# ft4222h.net
KiCad netlist of a schematic drawn in EAGLE
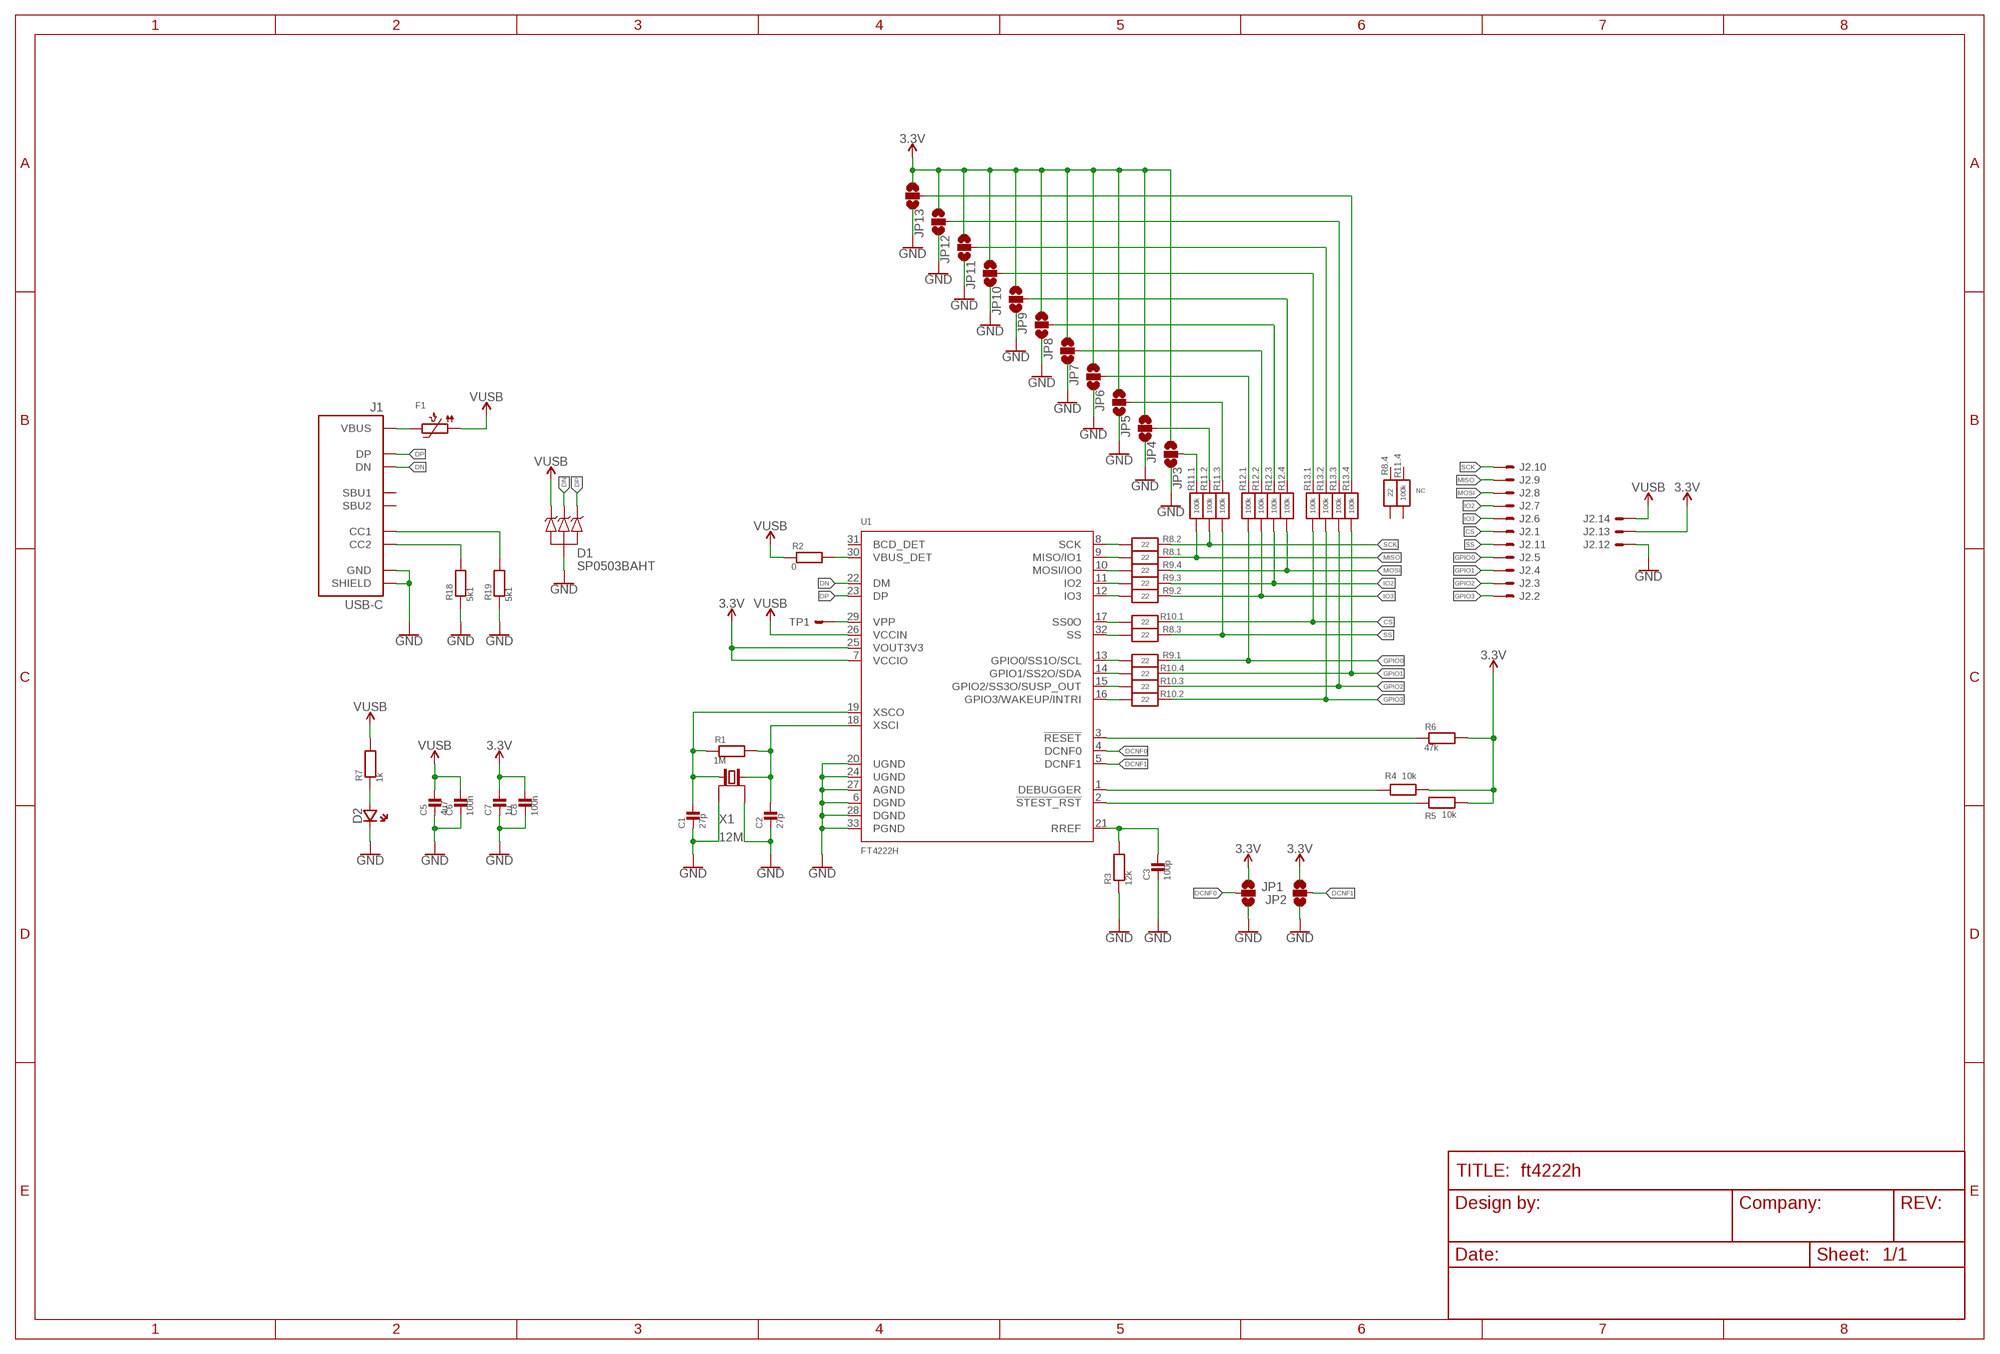
[diagram p0: schematic, sheet 1]

(export (version "E")
  (design (tool "Eeschema 10.0.6"))
  (components
    (comp (ref "C1")
      (value "27p")
      (footprint "eagle-import:_0402")
      (libsource (lib "eagle-import") (part "MLCC_0402"))
    )
    (comp (ref "C2")
      (value "27p")
      (footprint "eagle-import:_0402")
      (libsource (lib "eagle-import") (part "MLCC_0402"))
    )
    (comp (ref "C3")
      (value "100p")
      (footprint "eagle-import:_0402")
      (libsource (lib "eagle-import") (part "MLCC_0402"))
    )
    (comp (ref "C5")
      (value "4u7")
      (footprint "eagle-import:0603_WAVE")
      (libsource (lib "eagle-import") (part "MLCC0603"))
    )
    (comp (ref "C6")
      (value "100n")
      (footprint "eagle-import:_0402")
      (libsource (lib "eagle-import") (part "MLCC_0402"))
    )
    (comp (ref "C7")
      (value "1u")
      (footprint "eagle-import:0603_WAVE")
      (libsource (lib "eagle-import") (part "MLCC0603"))
    )
    (comp (ref "C8")
      (value "100n")
      (footprint "eagle-import:_0402")
      (libsource (lib "eagle-import") (part "MLCC_0402"))
    )
    (comp (ref "D1")
      (value "SP0503BAHT")
      (footprint "eagle-import:SOT143")
      (libsource (lib "eagle-import") (part "SP0503BAHT"))
    )
    (comp (ref "D2")
      (value "LED0603")
      (footprint "eagle-import:CHIPLED_0603")
      (libsource (lib "eagle-import") (part "LED0603"))
    )
    (comp (ref "F1")
      (value "PTC0805")
      (footprint "eagle-import:0805")
      (libsource (lib "eagle-import") (part "PTC0805"))
    )
    (comp (ref "J1")
      (value "USB-C")
      (footprint "eagle-import:USB-C")
      (libsource (lib "eagle-import") (part "USB-C"))
    )
    (comp (ref "J2")
      (value "14")
      (footprint "eagle-import:2X7_2.54")
      (libsource (lib "eagle-import") (part "14"))
    )
    (comp (ref "JP1")
      (value "JUMPER-SMT_3_NO_SILK")
      (footprint "eagle-import:SMT-JUMPER_3_NO_SILK")
      (libsource (lib "eagle-import") (part "JUMPER-SMT_3_NO_SILK"))
    )
    (comp (ref "JP2")
      (value "JUMPER-SMT_3_NO_SILK")
      (footprint "eagle-import:SMT-JUMPER_3_NO_SILK")
      (libsource (lib "eagle-import") (part "JUMPER-SMT_3_NO_SILK"))
    )
    (comp (ref "JP3")
      (value "JUMPER-SMT_3_NO_SILK")
      (footprint "eagle-import:SMT-JUMPER_3_NO_SILK")
      (libsource (lib "eagle-import") (part "JUMPER-SMT_3_NO_SILK"))
    )
    (comp (ref "JP4")
      (value "JUMPER-SMT_3_NO_SILK")
      (footprint "eagle-import:SMT-JUMPER_3_NO_SILK")
      (libsource (lib "eagle-import") (part "JUMPER-SMT_3_NO_SILK"))
    )
    (comp (ref "JP5")
      (value "JUMPER-SMT_3_NO_SILK")
      (footprint "eagle-import:SMT-JUMPER_3_NO_SILK")
      (libsource (lib "eagle-import") (part "JUMPER-SMT_3_NO_SILK"))
    )
    (comp (ref "JP6")
      (value "JUMPER-SMT_3_NO_SILK")
      (footprint "eagle-import:SMT-JUMPER_3_NO_SILK")
      (libsource (lib "eagle-import") (part "JUMPER-SMT_3_NO_SILK"))
    )
    (comp (ref "JP7")
      (value "JUMPER-SMT_3_NO_SILK")
      (footprint "eagle-import:SMT-JUMPER_3_NO_SILK")
      (libsource (lib "eagle-import") (part "JUMPER-SMT_3_NO_SILK"))
    )
    (comp (ref "JP8")
      (value "JUMPER-SMT_3_NO_SILK")
      (footprint "eagle-import:SMT-JUMPER_3_NO_SILK")
      (libsource (lib "eagle-import") (part "JUMPER-SMT_3_NO_SILK"))
    )
    (comp (ref "JP9")
      (value "JUMPER-SMT_3_NO_SILK")
      (footprint "eagle-import:SMT-JUMPER_3_NO_SILK")
      (libsource (lib "eagle-import") (part "JUMPER-SMT_3_NO_SILK"))
    )
    (comp (ref "JP10")
      (value "JUMPER-SMT_3_NO_SILK")
      (footprint "eagle-import:SMT-JUMPER_3_NO_SILK")
      (libsource (lib "eagle-import") (part "JUMPER-SMT_3_NO_SILK"))
    )
    (comp (ref "JP11")
      (value "JUMPER-SMT_3_NO_SILK")
      (footprint "eagle-import:SMT-JUMPER_3_NO_SILK")
      (libsource (lib "eagle-import") (part "JUMPER-SMT_3_NO_SILK"))
    )
    (comp (ref "JP12")
      (value "JUMPER-SMT_3_NO_SILK")
      (footprint "eagle-import:SMT-JUMPER_3_NO_SILK")
      (libsource (lib "eagle-import") (part "JUMPER-SMT_3_NO_SILK"))
    )
    (comp (ref "JP13")
      (value "JUMPER-SMT_3_NO_SILK")
      (footprint "eagle-import:SMT-JUMPER_3_NO_SILK")
      (libsource (lib "eagle-import") (part "JUMPER-SMT_3_NO_SILK"))
    )
    (comp (ref "R1")
      (value "1M")
      (footprint "eagle-import:_0402")
      (libsource (lib "eagle-import") (part "RESISTOR_0402"))
    )
    (comp (ref "R2")
      (value "0")
      (footprint "eagle-import:_0402")
      (libsource (lib "eagle-import") (part "RESISTOR_0402"))
    )
    (comp (ref "R3")
      (value "12k")
      (footprint "eagle-import:_0402")
      (libsource (lib "eagle-import") (part "RESISTOR_0402"))
    )
    (comp (ref "R4")
      (value "10k")
      (footprint "eagle-import:_0402")
      (libsource (lib "eagle-import") (part "RESISTOR_0402"))
    )
    (comp (ref "R5")
      (value "10k")
      (footprint "eagle-import:_0402")
      (libsource (lib "eagle-import") (part "RESISTOR_0402"))
    )
    (comp (ref "R6")
      (value "47k")
      (footprint "eagle-import:_0402")
      (libsource (lib "eagle-import") (part "RESISTOR_0402"))
    )
    (comp (ref "R7")
      (value "1k")
      (footprint "eagle-import:_0402")
      (libsource (lib "eagle-import") (part "RESISTOR_0402"))
    )
    (comp (ref "R8")
      (value "22")
      (footprint "eagle-import:RESPACK_4X0603")
      (libsource (lib "eagle-import") (part "RESISTOR_4PACK"))
    )
    (comp (ref "R9")
      (value "22")
      (footprint "eagle-import:RESPACK_4X0603")
      (libsource (lib "eagle-import") (part "RESISTOR_4PACK"))
    )
    (comp (ref "R10")
      (value "22")
      (footprint "eagle-import:RESPACK_4X0603")
      (libsource (lib "eagle-import") (part "RESISTOR_4PACK"))
    )
    (comp (ref "R11")
      (value "100k")
      (footprint "eagle-import:RESPACK_4X0603")
      (libsource (lib "eagle-import") (part "RESISTOR_4PACK"))
    )
    (comp (ref "R12")
      (value "100k")
      (footprint "eagle-import:RESPACK_4X0603")
      (libsource (lib "eagle-import") (part "RESISTOR_4PACK"))
    )
    (comp (ref "R13")
      (value "100k")
      (footprint "eagle-import:RESPACK_4X0603")
      (libsource (lib "eagle-import") (part "RESISTOR_4PACK"))
    )
    (comp (ref "R18")
      (value "5k1")
      (footprint "eagle-import:_0402")
      (libsource (lib "eagle-import") (part "RESISTOR_0402"))
    )
    (comp (ref "R19")
      (value "5k1")
      (footprint "eagle-import:_0402")
      (libsource (lib "eagle-import") (part "RESISTOR_0402"))
    )
    (comp (ref "TP1")
      (value "TEST_POINT")
      (footprint "eagle-import:TEST_POINT")
      (libsource (lib "eagle-import") (part "TEST_POINT"))
    )
    (comp (ref "U1")
      (value "FT4222H")
      (footprint "eagle-import:QFN32")
      (libsource (lib "eagle-import") (part "FT4222H"))
    )
    (comp (ref "X1")
      (value "12M")
      (footprint "eagle-import:4-SMD-3225")
      (libsource (lib "eagle-import") (part "CRYSTAL_4P"))
    )
  )
  (nets
    (net (code "1") (name "3.3V") (class "Default")
      (node (ref "C7") (pin "P$1") (pinfunction "P$1_P$1") (pintype "bidirectional"))
      (node (ref "C8") (pin "1") (pinfunction "P$1_1") (pintype "bidirectional"))
      (node (ref "J2") (pin "13") (pinfunction "S_13") (pintype "passive"))
      (node (ref "JP1") (pin "1") (pinfunction "1_1") (pintype "passive"))
      (node (ref "JP10") (pin "3") (pinfunction "3_3") (pintype "passive"))
      (node (ref "JP11") (pin "3") (pinfunction "3_3") (pintype "passive"))
      (node (ref "JP12") (pin "3") (pinfunction "3_3") (pintype "passive"))
      (node (ref "JP13") (pin "3") (pinfunction "3_3") (pintype "passive"))
      (node (ref "JP2") (pin "3") (pinfunction "3_3") (pintype "passive"))
      (node (ref "JP3") (pin "3") (pinfunction "3_3") (pintype "passive"))
      (node (ref "JP4") (pin "3") (pinfunction "3_3") (pintype "passive"))
      (node (ref "JP5") (pin "3") (pinfunction "3_3") (pintype "passive"))
      (node (ref "JP6") (pin "3") (pinfunction "3_3") (pintype "passive"))
      (node (ref "JP7") (pin "3") (pinfunction "3_3") (pintype "passive"))
      (node (ref "JP8") (pin "3") (pinfunction "3_3") (pintype "passive"))
      (node (ref "JP9") (pin "3") (pinfunction "3_3") (pintype "passive"))
      (node (ref "R4") (pin "2") (pinfunction "P$2_2") (pintype "bidirectional"))
      (node (ref "R5") (pin "2") (pinfunction "P$2_2") (pintype "bidirectional"))
      (node (ref "R6") (pin "2") (pinfunction "P$2_2") (pintype "bidirectional"))
      (node (ref "U1") (pin "25") (pinfunction "VOUT3V3_25") (pintype "bidirectional"))
      (node (ref "U1") (pin "7") (pinfunction "VCCIO_7") (pintype "bidirectional"))
    )
    (net (code "2") (name "CS") (class "Default")
      (node (ref "J2") (pin "1") (pinfunction "S_1") (pintype "passive"))
      (node (ref "R10") (pin "8") (pinfunction "2_8") (pintype "passive"))
      (node (ref "R13") (pin "1") (pinfunction "1_1") (pintype "passive"))
    )
    (net (code "3") (name "DCNF0") (class "Default")
      (node (ref "JP1") (pin "2") (pinfunction "2_2") (pintype "passive"))
      (node (ref "U1") (pin "4") (pinfunction "DCNF0_4") (pintype "bidirectional"))
    )
    (net (code "4") (name "DCNF1") (class "Default")
      (node (ref "JP2") (pin "2") (pinfunction "2_2") (pintype "passive"))
      (node (ref "U1") (pin "5") (pinfunction "DCNF1_5") (pintype "bidirectional"))
    )
    (net (code "5") (name "DN") (class "Default")
      (node (ref "D1") (pin "3") (pinfunction "3_3") (pintype "bidirectional"))
      (node (ref "J1") (pin "A7") (pinfunction "DN_A7") (pintype "bidirectional"))
      (node (ref "J1") (pin "B7") (pinfunction "DN_B7") (pintype "bidirectional"))
      (node (ref "U1") (pin "22") (pinfunction "DM_22") (pintype "bidirectional"))
    )
    (net (code "6") (name "DP") (class "Default")
      (node (ref "D1") (pin "4") (pinfunction "4_4") (pintype "bidirectional"))
      (node (ref "J1") (pin "A6") (pinfunction "DP_A6") (pintype "bidirectional"))
      (node (ref "J1") (pin "B6") (pinfunction "DP_B6") (pintype "bidirectional"))
      (node (ref "U1") (pin "23") (pinfunction "DP_23") (pintype "bidirectional"))
    )
    (net (code "7") (name "GND") (class "Default")
      (node (ref "C1") (pin "2") (pinfunction "P$2_2") (pintype "bidirectional"))
      (node (ref "C2") (pin "2") (pinfunction "P$2_2") (pintype "bidirectional"))
      (node (ref "C3") (pin "2") (pinfunction "P$2_2") (pintype "bidirectional"))
      (node (ref "C5") (pin "P$2") (pinfunction "P$2_P$2") (pintype "bidirectional"))
      (node (ref "C6") (pin "2") (pinfunction "P$2_2") (pintype "bidirectional"))
      (node (ref "C7") (pin "P$2") (pinfunction "P$2_P$2") (pintype "bidirectional"))
      (node (ref "C8") (pin "2") (pinfunction "P$2_2") (pintype "bidirectional"))
      (node (ref "D1") (pin "1") (pinfunction "1_1") (pintype "bidirectional"))
      (node (ref "D2") (pin "C") (pinfunction "CA_C") (pintype "bidirectional"))
      (node (ref "J1") (pin "A1/B12") (pinfunction "GND_A1/B12") (pintype "bidirectional"))
      (node (ref "J1") (pin "B1/A12") (pinfunction "GND_B1/A12") (pintype "bidirectional"))
      (node (ref "J1") (pin "SHIELD0") (pinfunction "SHIELD_SHIELD0") (pintype "bidirectional"))
      (node (ref "J1") (pin "SHIELD1") (pinfunction "SHIELD_SHIELD1") (pintype "bidirectional"))
      (node (ref "J1") (pin "SHIELD2") (pinfunction "SHIELD_SHIELD2") (pintype "bidirectional"))
      (node (ref "J1") (pin "SHIELD3") (pinfunction "SHIELD_SHIELD3") (pintype "bidirectional"))
      (node (ref "J2") (pin "12") (pinfunction "S_12") (pintype "passive"))
      (node (ref "JP1") (pin "3") (pinfunction "3_3") (pintype "passive"))
      (node (ref "JP10") (pin "1") (pinfunction "1_1") (pintype "passive"))
      (node (ref "JP11") (pin "1") (pinfunction "1_1") (pintype "passive"))
      (node (ref "JP12") (pin "1") (pinfunction "1_1") (pintype "passive"))
      (node (ref "JP13") (pin "1") (pinfunction "1_1") (pintype "passive"))
      (node (ref "JP2") (pin "1") (pinfunction "1_1") (pintype "passive"))
      (node (ref "JP3") (pin "1") (pinfunction "1_1") (pintype "passive"))
      (node (ref "JP4") (pin "1") (pinfunction "1_1") (pintype "passive"))
      (node (ref "JP5") (pin "1") (pinfunction "1_1") (pintype "passive"))
      (node (ref "JP6") (pin "1") (pinfunction "1_1") (pintype "passive"))
      (node (ref "JP7") (pin "1") (pinfunction "1_1") (pintype "passive"))
      (node (ref "JP8") (pin "1") (pinfunction "1_1") (pintype "passive"))
      (node (ref "JP9") (pin "1") (pinfunction "1_1") (pintype "passive"))
      (node (ref "R18") (pin "1") (pinfunction "P$1_1") (pintype "bidirectional"))
      (node (ref "R19") (pin "1") (pinfunction "P$1_1") (pintype "bidirectional"))
      (node (ref "R3") (pin "1") (pinfunction "P$1_1") (pintype "bidirectional"))
      (node (ref "U1") (pin "20") (pinfunction "UGND_20") (pintype "bidirectional"))
      (node (ref "U1") (pin "24") (pinfunction "UGND_24") (pintype "bidirectional"))
      (node (ref "U1") (pin "27") (pinfunction "AGND_27") (pintype "bidirectional"))
      (node (ref "U1") (pin "28") (pinfunction "DGND_28") (pintype "bidirectional"))
      (node (ref "U1") (pin "33") (pinfunction "PGND_33") (pintype "bidirectional"))
      (node (ref "U1") (pin "6") (pinfunction "DGND_6") (pintype "bidirectional"))
      (node (ref "X1") (pin "2") (pinfunction "GND_2") (pintype "passive"))
      (node (ref "X1") (pin "4") (pinfunction "GND_4") (pintype "passive"))
    )
    (net (code "8") (name "GPIO0") (class "Default")
      (node (ref "J2") (pin "5") (pinfunction "S_5") (pintype "passive"))
      (node (ref "R12") (pin "1") (pinfunction "1_1") (pintype "passive"))
      (node (ref "R9") (pin "8") (pinfunction "2_8") (pintype "passive"))
    )
    (net (code "9") (name "GPIO1") (class "Default")
      (node (ref "J2") (pin "4") (pinfunction "S_4") (pintype "passive"))
      (node (ref "R10") (pin "5") (pinfunction "2_5") (pintype "passive"))
      (node (ref "R13") (pin "4") (pinfunction "1_4") (pintype "passive"))
    )
    (net (code "10") (name "GPIO2") (class "Default")
      (node (ref "J2") (pin "3") (pinfunction "S_3") (pintype "passive"))
      (node (ref "R10") (pin "6") (pinfunction "2_6") (pintype "passive"))
      (node (ref "R13") (pin "3") (pinfunction "1_3") (pintype "passive"))
    )
    (net (code "11") (name "GPIO3") (class "Default")
      (node (ref "J2") (pin "2") (pinfunction "S_2") (pintype "passive"))
      (node (ref "R10") (pin "7") (pinfunction "2_7") (pintype "passive"))
      (node (ref "R13") (pin "2") (pinfunction "1_2") (pintype "passive"))
    )
    (net (code "12") (name "IO2") (class "Default")
      (node (ref "J2") (pin "7") (pinfunction "S_7") (pintype "passive"))
      (node (ref "R12") (pin "3") (pinfunction "1_3") (pintype "passive"))
      (node (ref "R9") (pin "6") (pinfunction "2_6") (pintype "passive"))
    )
    (net (code "13") (name "IO3") (class "Default")
      (node (ref "J2") (pin "6") (pinfunction "S_6") (pintype "passive"))
      (node (ref "R12") (pin "2") (pinfunction "1_2") (pintype "passive"))
      (node (ref "R9") (pin "7") (pinfunction "2_7") (pintype "passive"))
    )
    (net (code "14") (name "MISO") (class "Default")
      (node (ref "J2") (pin "9") (pinfunction "S_9") (pintype "passive"))
      (node (ref "R11") (pin "1") (pinfunction "1_1") (pintype "passive"))
      (node (ref "R8") (pin "8") (pinfunction "2_8") (pintype "passive"))
    )
    (net (code "15") (name "MOSI") (class "Default")
      (node (ref "J2") (pin "8") (pinfunction "S_8") (pintype "passive"))
      (node (ref "R12") (pin "4") (pinfunction "1_4") (pintype "passive"))
      (node (ref "R9") (pin "5") (pinfunction "2_5") (pintype "passive"))
    )
    (net (code "16") (name "Net-(C1-P$1)") (class "Default")
      (node (ref "C1") (pin "1") (pinfunction "P$1_1") (pintype "bidirectional"))
      (node (ref "R1") (pin "1") (pinfunction "P$1_1") (pintype "bidirectional"))
      (node (ref "U1") (pin "19") (pinfunction "XSCO_19") (pintype "bidirectional"))
      (node (ref "X1") (pin "1") (pinfunction "1_1") (pintype "passive"))
    )
    (net (code "17") (name "Net-(C2-P$1)") (class "Default")
      (node (ref "C2") (pin "1") (pinfunction "P$1_1") (pintype "bidirectional"))
      (node (ref "R1") (pin "2") (pinfunction "P$2_2") (pintype "bidirectional"))
      (node (ref "U1") (pin "18") (pinfunction "XSCI_18") (pintype "bidirectional"))
      (node (ref "X1") (pin "3") (pinfunction "2_3") (pintype "passive"))
    )
    (net (code "18") (name "Net-(C3-P$1)") (class "Default")
      (node (ref "C3") (pin "1") (pinfunction "P$1_1") (pintype "bidirectional"))
      (node (ref "R3") (pin "2") (pinfunction "P$2_2") (pintype "bidirectional"))
      (node (ref "U1") (pin "21") (pinfunction "RREF_21") (pintype "bidirectional"))
    )
    (net (code "19") (name "Net-(D2-AN)") (class "Default")
      (node (ref "D2") (pin "A") (pinfunction "AN_A") (pintype "bidirectional"))
      (node (ref "R7") (pin "1") (pinfunction "P$1_1") (pintype "bidirectional"))
    )
    (net (code "20") (name "Net-(F1-Pad2)") (class "Default")
      (node (ref "F1") (pin "2") (pinfunction "2_2") (pintype "passive"))
      (node (ref "J1") (pin "A4/B9") (pinfunction "VBUS_A4/B9") (pintype "bidirectional"))
      (node (ref "J1") (pin "B4/A9") (pinfunction "VBUS_B4/A9") (pintype "bidirectional"))
    )
    (net (code "21") (name "Net-(J1-CC1)") (class "Default")
      (node (ref "J1") (pin "A5") (pinfunction "CC1_A5") (pintype "bidirectional"))
      (node (ref "R19") (pin "2") (pinfunction "P$2_2") (pintype "bidirectional"))
    )
    (net (code "22") (name "Net-(J1-CC2)") (class "Default")
      (node (ref "J1") (pin "B5") (pinfunction "CC2_B5") (pintype "bidirectional"))
      (node (ref "R18") (pin "2") (pinfunction "P$2_2") (pintype "bidirectional"))
    )
    (net (code "23") (name "Net-(R2-P$2)") (class "Default")
      (node (ref "R2") (pin "2") (pinfunction "P$2_2") (pintype "bidirectional"))
      (node (ref "U1") (pin "30") (pinfunction "VBUS_DET_30") (pintype "bidirectional"))
    )
    (net (code "24") (name "Net-(R4-P$1)") (class "Default")
      (node (ref "R4") (pin "1") (pinfunction "P$1_1") (pintype "bidirectional"))
      (node (ref "U1") (pin "1") (pinfunction "DEBUGGER_1") (pintype "bidirectional"))
    )
    (net (code "25") (name "Net-(R5-P$1)") (class "Default")
      (node (ref "R5") (pin "1") (pinfunction "P$1_1") (pintype "bidirectional"))
      (node (ref "U1") (pin "2") (pinfunction "~{STEST_RST}_2") (pintype "bidirectional"))
    )
    (net (code "26") (name "Net-(R6-P$1)") (class "Default")
      (node (ref "R6") (pin "1") (pinfunction "P$1_1") (pintype "bidirectional"))
      (node (ref "U1") (pin "3") (pinfunction "~{RESET}_3") (pintype "bidirectional"))
    )
    (net (code "27") (name "Net-(R8B-1)") (class "Default")
      (node (ref "R8") (pin "2") (pinfunction "1_2") (pintype "passive"))
      (node (ref "U1") (pin "8") (pinfunction "SCK_8") (pintype "bidirectional"))
    )
    (net (code "28") (name "Net-(R8C-1)") (class "Default")
      (node (ref "R8") (pin "3") (pinfunction "1_3") (pintype "passive"))
      (node (ref "U1") (pin "32") (pinfunction "SS_32") (pintype "bidirectional"))
    )
    (net (code "29") (name "Net-(R9B-1)") (class "Default")
      (node (ref "R9") (pin "2") (pinfunction "1_2") (pintype "passive"))
      (node (ref "U1") (pin "12") (pinfunction "IO3_12") (pintype "bidirectional"))
    )
    (net (code "30") (name "Net-(R9C-1)") (class "Default")
      (node (ref "R9") (pin "3") (pinfunction "1_3") (pintype "passive"))
      (node (ref "U1") (pin "11") (pinfunction "IO2_11") (pintype "bidirectional"))
    )
    (net (code "31") (name "Net-(R9D-1)") (class "Default")
      (node (ref "R9") (pin "4") (pinfunction "1_4") (pintype "passive"))
      (node (ref "U1") (pin "10") (pinfunction "MOSI/IO0_10") (pintype "bidirectional"))
    )
    (net (code "32") (name "Net-(R10B-1)") (class "Default")
      (node (ref "R10") (pin "2") (pinfunction "1_2") (pintype "passive"))
      (node (ref "U1") (pin "16") (pinfunction "GPIO3/WAKEUP/INTRI_16") (pintype "bidirectional"))
    )
    (net (code "33") (name "Net-(R10C-1)") (class "Default")
      (node (ref "R10") (pin "3") (pinfunction "1_3") (pintype "passive"))
      (node (ref "U1") (pin "15") (pinfunction "GPIO2/SS3O/SUSP_OUT_15") (pintype "bidirectional"))
    )
    (net (code "34") (name "Net-(R10D-1)") (class "Default")
      (node (ref "R10") (pin "4") (pinfunction "1_4") (pintype "passive"))
      (node (ref "U1") (pin "14") (pinfunction "GPIO1/SS2O/SDA_14") (pintype "bidirectional"))
    )
    (net (code "35") (name "Net-(R11A-2)") (class "Default")
      (node (ref "JP3") (pin "2") (pinfunction "2_2") (pintype "passive"))
      (node (ref "R11") (pin "8") (pinfunction "2_8") (pintype "passive"))
    )
    (net (code "36") (name "Net-(R11B-2)") (class "Default")
      (node (ref "JP4") (pin "2") (pinfunction "2_2") (pintype "passive"))
      (node (ref "R11") (pin "7") (pinfunction "2_7") (pintype "passive"))
    )
    (net (code "37") (name "Net-(R11C-2)") (class "Default")
      (node (ref "JP5") (pin "2") (pinfunction "2_2") (pintype "passive"))
      (node (ref "R11") (pin "6") (pinfunction "2_6") (pintype "passive"))
    )
    (net (code "38") (name "Net-(R12A-2)") (class "Default")
      (node (ref "JP6") (pin "2") (pinfunction "2_2") (pintype "passive"))
      (node (ref "R12") (pin "8") (pinfunction "2_8") (pintype "passive"))
    )
    (net (code "39") (name "Net-(R12B-2)") (class "Default")
      (node (ref "JP7") (pin "2") (pinfunction "2_2") (pintype "passive"))
      (node (ref "R12") (pin "7") (pinfunction "2_7") (pintype "passive"))
    )
    (net (code "40") (name "Net-(R12C-2)") (class "Default")
      (node (ref "JP8") (pin "2") (pinfunction "2_2") (pintype "passive"))
      (node (ref "R12") (pin "6") (pinfunction "2_6") (pintype "passive"))
    )
    (net (code "41") (name "Net-(R12D-2)") (class "Default")
      (node (ref "JP9") (pin "2") (pinfunction "2_2") (pintype "passive"))
      (node (ref "R12") (pin "5") (pinfunction "2_5") (pintype "passive"))
    )
    (net (code "42") (name "Net-(R13A-2)") (class "Default")
      (node (ref "JP10") (pin "2") (pinfunction "2_2") (pintype "passive"))
      (node (ref "R13") (pin "8") (pinfunction "2_8") (pintype "passive"))
    )
    (net (code "43") (name "Net-(R13B-2)") (class "Default")
      (node (ref "JP11") (pin "2") (pinfunction "2_2") (pintype "passive"))
      (node (ref "R13") (pin "7") (pinfunction "2_7") (pintype "passive"))
    )
    (net (code "44") (name "Net-(R13C-2)") (class "Default")
      (node (ref "JP12") (pin "2") (pinfunction "2_2") (pintype "passive"))
      (node (ref "R13") (pin "6") (pinfunction "2_6") (pintype "passive"))
    )
    (net (code "45") (name "Net-(R13D-2)") (class "Default")
      (node (ref "JP13") (pin "2") (pinfunction "2_2") (pintype "passive"))
      (node (ref "R13") (pin "5") (pinfunction "2_5") (pintype "passive"))
    )
    (net (code "46") (name "Net-(TP1-S)") (class "Default")
      (node (ref "TP1") (pin "1") (pinfunction "S_1") (pintype "passive"))
      (node (ref "U1") (pin "29") (pinfunction "VPP_29") (pintype "bidirectional"))
    )
    (net (code "47") (name "Net-(U1-GPIO0{slash}SS1O{slash}SCL)") (class "Default")
      (node (ref "R9") (pin "1") (pinfunction "1_1") (pintype "passive"))
      (node (ref "U1") (pin "13") (pinfunction "GPIO0/SS1O/SCL_13") (pintype "bidirectional"))
    )
    (net (code "48") (name "Net-(U1-MISO{slash}IO1)") (class "Default")
      (node (ref "R8") (pin "1") (pinfunction "1_1") (pintype "passive"))
      (node (ref "U1") (pin "9") (pinfunction "MISO/IO1_9") (pintype "bidirectional"))
    )
    (net (code "49") (name "Net-(U1-SS0O)") (class "Default")
      (node (ref "R10") (pin "1") (pinfunction "1_1") (pintype "passive"))
      (node (ref "U1") (pin "17") (pinfunction "SS0O_17") (pintype "bidirectional"))
    )
    (net (code "50") (name "SCK") (class "Default")
      (node (ref "J2") (pin "10") (pinfunction "S_10") (pintype "passive"))
      (node (ref "R11") (pin "2") (pinfunction "1_2") (pintype "passive"))
      (node (ref "R8") (pin "7") (pinfunction "2_7") (pintype "passive"))
    )
    (net (code "51") (name "SS") (class "Default")
      (node (ref "J2") (pin "11") (pinfunction "S_11") (pintype "passive"))
      (node (ref "R11") (pin "3") (pinfunction "1_3") (pintype "passive"))
      (node (ref "R8") (pin "6") (pinfunction "2_6") (pintype "passive"))
    )
    (net (code "52") (name "VUSB") (class "Default")
      (node (ref "C5") (pin "P$1") (pinfunction "P$1_P$1") (pintype "bidirectional"))
      (node (ref "C6") (pin "1") (pinfunction "P$1_1") (pintype "bidirectional"))
      (node (ref "D1") (pin "2") (pinfunction "2_2") (pintype "bidirectional"))
      (node (ref "F1") (pin "1") (pinfunction "1_1") (pintype "passive"))
      (node (ref "J2") (pin "14") (pinfunction "S_14") (pintype "passive"))
      (node (ref "R2") (pin "1") (pinfunction "P$1_1") (pintype "bidirectional"))
      (node (ref "R7") (pin "2") (pinfunction "P$2_2") (pintype "bidirectional"))
      (node (ref "U1") (pin "26") (pinfunction "VCCIN_26") (pintype "bidirectional"))
    )
    (net (code "53") (name "unconnected-(J1-SBU1-PadA8)") (class "Default")
      (node (ref "J1") (pin "A8") (pinfunction "SBU1_A8") (pintype "bidirectional"))
    )
    (net (code "54") (name "unconnected-(J1-SBU2-PadB8)") (class "Default")
      (node (ref "J1") (pin "B8") (pinfunction "SBU2_B8") (pintype "bidirectional"))
    )
    (net (code "55") (name "unconnected-(R8D-1-Pad4)") (class "Default")
      (node (ref "R8") (pin "4") (pinfunction "1_4") (pintype "passive"))
    )
    (net (code "56") (name "unconnected-(R8D-2-Pad5)") (class "Default")
      (node (ref "R8") (pin "5") (pinfunction "2_5") (pintype "passive"))
    )
    (net (code "57") (name "unconnected-(R11D-1-Pad4)") (class "Default")
      (node (ref "R11") (pin "4") (pinfunction "1_4") (pintype "passive"))
    )
    (net (code "58") (name "unconnected-(R11D-2-Pad5)") (class "Default")
      (node (ref "R11") (pin "5") (pinfunction "2_5") (pintype "passive"))
    )
    (net (code "59") (name "unconnected-(U1-BCD_DET-Pad31)") (class "Default")
      (node (ref "U1") (pin "31") (pinfunction "BCD_DET_31") (pintype "bidirectional"))
    )
  )
)
